# SDRAM.net
KiCad netlist of a schematic drawn in Altium Designer
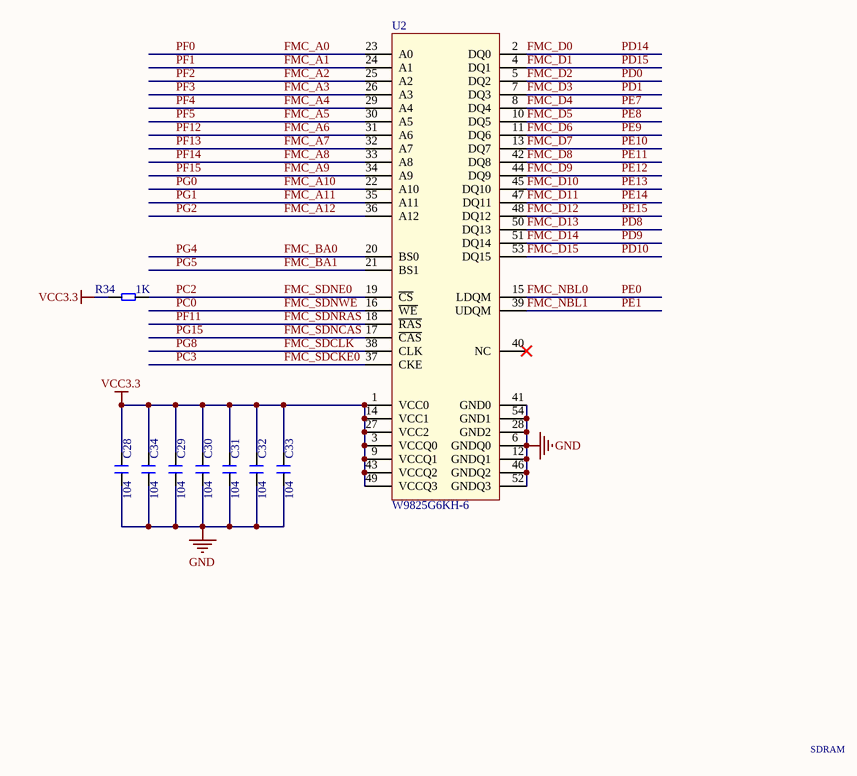
[diagram p0: SDRAM.SchDoc]

(export (version "E")
  (design (tool "Eeschema 10.0.6"))
  (components
    (comp (ref "C28") (value "104") (footprint "C 0603") (libsource (lib "Bison-Board") (part "CAP")))
    (comp (ref "C29") (value "104") (footprint "C 0603") (libsource (lib "Bison-Board") (part "CAP")))
    (comp (ref "C30") (value "104") (footprint "C 0603") (libsource (lib "Bison-Board") (part "CAP")))
    (comp (ref "C31") (value "104") (footprint "C 0603") (libsource (lib "Bison-Board") (part "CAP")))
    (comp (ref "C32") (value "104") (footprint "C 0603") (libsource (lib "Bison-Board") (part "CAP")))
    (comp (ref "C33") (value "104") (footprint "C 0603") (libsource (lib "Bison-Board") (part "CAP")))
    (comp (ref "C34") (value "104") (footprint "C 0603") (libsource (lib "Bison-Board") (part "CAP")))
    (comp (ref "R34") (value "1K") (footprint "R 0603") (libsource (lib "Bison-Board") (part "RES")))
    (comp (ref "U2")
      (value "W9825G6KH-6")
      (footprint "TSOP54")
      (libsource (lib "Bison-Board") (part "W9825G6KH-6"))
    )
  )
  (nets
    (net (code "1") (name "/FMC_A0") (class "Default")
      (node (ref "U2") (pin "23") (pinfunction "A0_23") (pintype "passive"))
    )
    (net (code "2") (name "/FMC_A1") (class "Default")
      (node (ref "U2") (pin "24") (pinfunction "A1_24") (pintype "passive"))
    )
    (net (code "3") (name "/FMC_A2") (class "Default")
      (node (ref "U2") (pin "25") (pinfunction "A2_25") (pintype "passive"))
    )
    (net (code "4") (name "/FMC_A3") (class "Default")
      (node (ref "U2") (pin "26") (pinfunction "A3_26") (pintype "passive"))
    )
    (net (code "5") (name "/FMC_A4") (class "Default")
      (node (ref "U2") (pin "29") (pinfunction "A4_29") (pintype "passive"))
    )
    (net (code "6") (name "/FMC_A5") (class "Default")
      (node (ref "U2") (pin "30") (pinfunction "A5_30") (pintype "passive"))
    )
    (net (code "7") (name "/FMC_A6") (class "Default")
      (node (ref "U2") (pin "31") (pinfunction "A6_31") (pintype "passive"))
    )
    (net (code "8") (name "/FMC_A7") (class "Default")
      (node (ref "U2") (pin "32") (pinfunction "A7_32") (pintype "passive"))
    )
    (net (code "9") (name "/FMC_A8") (class "Default")
      (node (ref "U2") (pin "33") (pinfunction "A8_33") (pintype "passive"))
    )
    (net (code "10") (name "/FMC_A9") (class "Default")
      (node (ref "U2") (pin "34") (pinfunction "A9_34") (pintype "passive"))
    )
    (net (code "11") (name "/FMC_A10") (class "Default")
      (node (ref "U2") (pin "22") (pinfunction "A10_22") (pintype "passive"))
    )
    (net (code "12") (name "/FMC_A11") (class "Default")
      (node (ref "U2") (pin "35") (pinfunction "A11_35") (pintype "passive"))
    )
    (net (code "13") (name "/FMC_A12") (class "Default")
      (node (ref "U2") (pin "36") (pinfunction "A12_36") (pintype "passive"))
    )
    (net (code "14") (name "/FMC_BA0") (class "Default")
      (node (ref "U2") (pin "20") (pinfunction "BS0_20") (pintype "passive"))
    )
    (net (code "15") (name "/FMC_BA1") (class "Default")
      (node (ref "U2") (pin "21") (pinfunction "BS1_21") (pintype "passive"))
    )
    (net (code "16") (name "/FMC_D0") (class "Default")
      (node (ref "U2") (pin "2") (pinfunction "DQ0_2") (pintype "passive"))
    )
    (net (code "17") (name "/FMC_D1") (class "Default")
      (node (ref "U2") (pin "4") (pinfunction "DQ1_4") (pintype "passive"))
    )
    (net (code "18") (name "/FMC_D2") (class "Default")
      (node (ref "U2") (pin "5") (pinfunction "DQ2_5") (pintype "passive"))
    )
    (net (code "19") (name "/FMC_D3") (class "Default")
      (node (ref "U2") (pin "7") (pinfunction "DQ3_7") (pintype "passive"))
    )
    (net (code "20") (name "/FMC_D4") (class "Default")
      (node (ref "U2") (pin "8") (pinfunction "DQ4_8") (pintype "passive"))
    )
    (net (code "21") (name "/FMC_D5") (class "Default")
      (node (ref "U2") (pin "10") (pinfunction "DQ5_10") (pintype "passive"))
    )
    (net (code "22") (name "/FMC_D6") (class "Default")
      (node (ref "U2") (pin "11") (pinfunction "DQ6_11") (pintype "passive"))
    )
    (net (code "23") (name "/FMC_D7") (class "Default")
      (node (ref "U2") (pin "13") (pinfunction "DQ7_13") (pintype "passive"))
    )
    (net (code "24") (name "/FMC_D8") (class "Default")
      (node (ref "U2") (pin "42") (pinfunction "DQ8_42") (pintype "passive"))
    )
    (net (code "25") (name "/FMC_D9") (class "Default")
      (node (ref "U2") (pin "44") (pinfunction "DQ9_44") (pintype "passive"))
    )
    (net (code "26") (name "/FMC_D10") (class "Default")
      (node (ref "U2") (pin "45") (pinfunction "DQ10_45") (pintype "passive"))
    )
    (net (code "27") (name "/FMC_D11") (class "Default")
      (node (ref "U2") (pin "47") (pinfunction "DQ11_47") (pintype "passive"))
    )
    (net (code "28") (name "/FMC_D12") (class "Default")
      (node (ref "U2") (pin "48") (pinfunction "DQ12_48") (pintype "passive"))
    )
    (net (code "29") (name "/FMC_D13") (class "Default")
      (node (ref "U2") (pin "50") (pinfunction "DQ13_50") (pintype "passive"))
    )
    (net (code "30") (name "/FMC_D14") (class "Default")
      (node (ref "U2") (pin "51") (pinfunction "DQ14_51") (pintype "passive"))
    )
    (net (code "31") (name "/FMC_D15") (class "Default")
      (node (ref "U2") (pin "53") (pinfunction "DQ15_53") (pintype "passive"))
    )
    (net (code "32") (name "/FMC_NBL0") (class "Default")
      (node (ref "U2") (pin "15") (pinfunction "LDQM_15") (pintype "passive"))
    )
    (net (code "33") (name "/FMC_NBL1") (class "Default")
      (node (ref "U2") (pin "39") (pinfunction "UDQM_39") (pintype "passive"))
    )
    (net (code "34") (name "/FMC_SDCKE0") (class "Default")
      (node (ref "U2") (pin "37") (pinfunction "CKE_37") (pintype "passive"))
    )
    (net (code "35") (name "/FMC_SDCLK") (class "Default")
      (node (ref "U2") (pin "38") (pinfunction "CLK_38") (pintype "passive"))
    )
    (net (code "36") (name "/FMC_SDNCAS") (class "Default")
      (node (ref "U2") (pin "17") (pinfunction "~{CAS}_17") (pintype "passive"))
    )
    (net (code "37") (name "/FMC_SDNE0") (class "Default")
      (node (ref "R34") (pin "2") (pintype "passive"))
      (node (ref "U2") (pin "19") (pinfunction "~{CS}_19") (pintype "passive"))
    )
    (net (code "38") (name "/FMC_SDNRAS") (class "Default")
      (node (ref "U2") (pin "18") (pinfunction "~{RAS}_18") (pintype "passive"))
    )
    (net (code "39") (name "/FMC_SDNWE") (class "Default")
      (node (ref "U2") (pin "16") (pinfunction "~{WE}_16") (pintype "passive"))
    )
    (net (code "40") (name "GND") (class "Default")
      (node (ref "C28") (pin "1") (pinfunction "1_1") (pintype "passive"))
      (node (ref "C29") (pin "1") (pinfunction "1_1") (pintype "passive"))
      (node (ref "C30") (pin "1") (pinfunction "1_1") (pintype "passive"))
      (node (ref "C31") (pin "1") (pinfunction "1_1") (pintype "passive"))
      (node (ref "C32") (pin "1") (pinfunction "1_1") (pintype "passive"))
      (node (ref "C33") (pin "1") (pinfunction "1_1") (pintype "passive"))
      (node (ref "C34") (pin "2") (pinfunction "2_2") (pintype "passive"))
      (node (ref "U2") (pin "12") (pinfunction "GNDQ1_12") (pintype "passive"))
      (node (ref "U2") (pin "28") (pinfunction "GND2_28") (pintype "passive"))
      (node (ref "U2") (pin "41") (pinfunction "GND0_41") (pintype "passive"))
      (node (ref "U2") (pin "46") (pinfunction "GNDQ2_46") (pintype "passive"))
      (node (ref "U2") (pin "52") (pinfunction "GNDQ3_52") (pintype "passive"))
      (node (ref "U2") (pin "54") (pinfunction "GND1_54") (pintype "passive"))
      (node (ref "U2") (pin "6") (pinfunction "GNDQ0_6") (pintype "passive"))
    )
    (net (code "41") (name "VCC3.3") (class "Default")
      (node (ref "C28") (pin "2") (pinfunction "2_2") (pintype "passive"))
      (node (ref "C29") (pin "2") (pinfunction "2_2") (pintype "passive"))
      (node (ref "C30") (pin "2") (pinfunction "2_2") (pintype "passive"))
      (node (ref "C31") (pin "2") (pinfunction "2_2") (pintype "passive"))
      (node (ref "C32") (pin "2") (pinfunction "2_2") (pintype "passive"))
      (node (ref "C33") (pin "2") (pinfunction "2_2") (pintype "passive"))
      (node (ref "C34") (pin "1") (pinfunction "1_1") (pintype "passive"))
      (node (ref "R34") (pin "1") (pintype "passive"))
      (node (ref "U2") (pin "1") (pinfunction "VCC0_1") (pintype "passive"))
      (node (ref "U2") (pin "14") (pinfunction "VCC1_14") (pintype "passive"))
      (node (ref "U2") (pin "27") (pinfunction "VCC2_27") (pintype "passive"))
      (node (ref "U2") (pin "3") (pinfunction "VCCQ0_3") (pintype "passive"))
      (node (ref "U2") (pin "43") (pinfunction "VCCQ2_43") (pintype "passive"))
      (node (ref "U2") (pin "49") (pinfunction "VCCQ3_49") (pintype "passive"))
      (node (ref "U2") (pin "9") (pinfunction "VCCQ1_9") (pintype "passive"))
    )
    (net (code "42") (name "unconnected-(U2-NC-Pad40)") (class "Default")
      (node (ref "U2") (pin "40") (pinfunction "NC_40") (pintype "passive+no_connect"))
    )
  )
)
